# rapidshark-main-breakout-top-mk-1_B.net
KiCad netlist of a schematic drawn in EAGLE
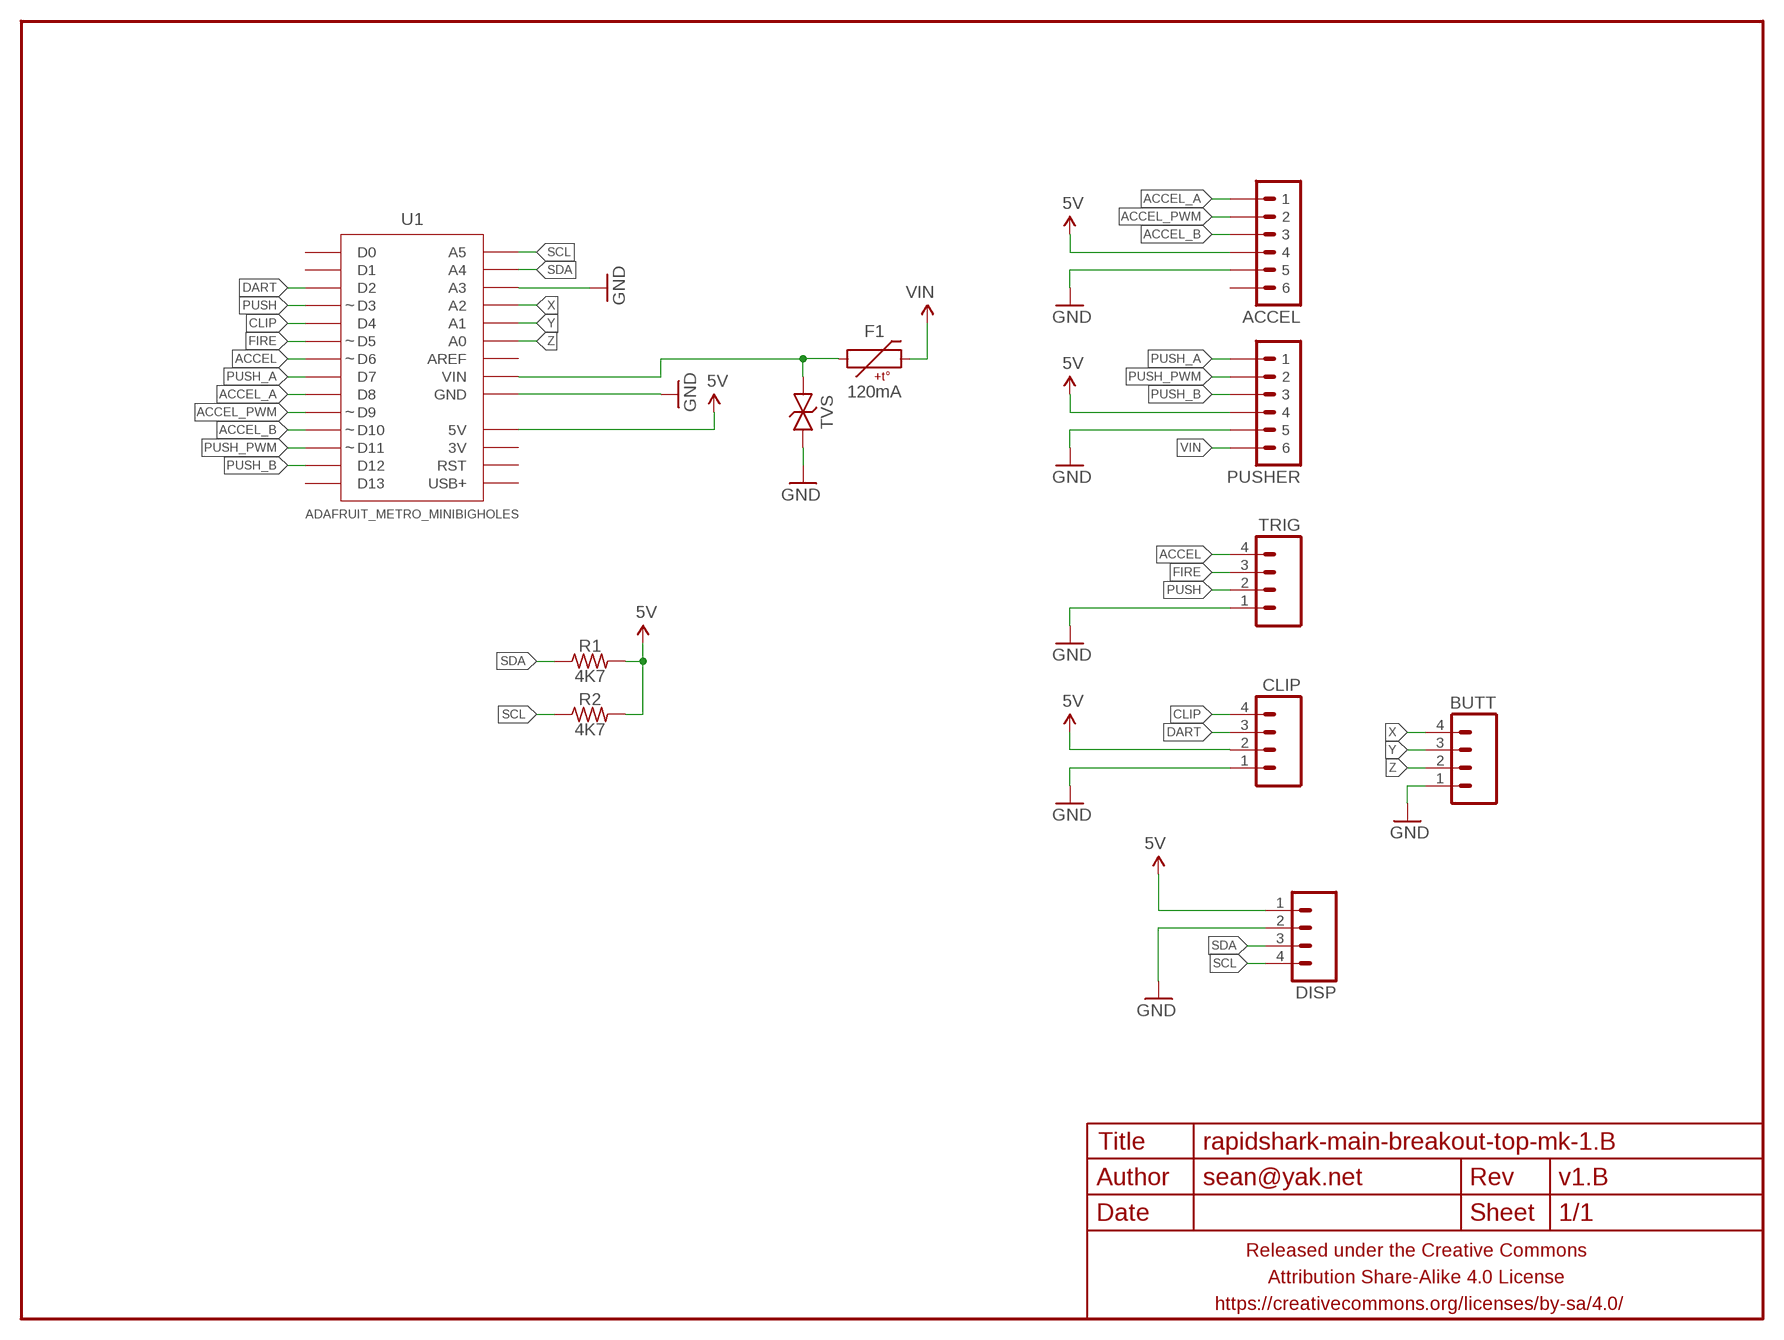
[diagram p0: schematic, sheet 1]

(export (version "E")
  (design (tool "Eeschema 10.0.6"))
  (components
    (comp (ref "ACCEL")
      (value "M06JST-PH-PTH-VERT")
      (footprint "eagle-import:JST-6-PH-VERT-PTH")
      (libsource (lib "eagle-import") (part "M06JST-PH-PTH-VERT"))
    )
    (comp (ref "BUTT")
      (value "M04JST-PTH-VERT")
      (footprint "eagle-import:JST-4-PH-VERT-PTH")
      (libsource (lib "eagle-import") (part "M04JST-PTH-VERT"))
    )
    (comp (ref "CLIP")
      (value "M04JST-PTH-VERT")
      (footprint "eagle-import:JST-4-PH-VERT-PTH")
      (libsource (lib "eagle-import") (part "M04JST-PTH-VERT"))
    )
    (comp (ref "DISP")
      (value "M04JST-PTH-VERT")
      (footprint "eagle-import:JST-4-PH-VERT-PTH")
      (libsource (lib "eagle-import") (part "M04JST-PTH-VERT"))
    )
    (comp (ref "F1")
      (value "120mA")
      (footprint "eagle-import:PTC-1206")
      (libsource (lib "eagle-import") (part "PTCSMD"))
    )
    (comp (ref "FRAME1")
      (value "FRAME-LETTERNO_PACKAGE")
      (footprint "eagle-import:DUMMY")
      (fields (field (name "DESIGNER") "sean@yak.net") (field (name "VERSION") "v1.B"))
      (libsource (lib "eagle-import") (part "FRAME-LETTERNO_PACKAGE"))
    )
    (comp (ref "PUSHER")
      (value "M06JST-PH-PTH-VERT")
      (footprint "eagle-import:JST-6-PH-VERT-PTH")
      (libsource (lib "eagle-import") (part "M06JST-PH-PTH-VERT"))
    )
    (comp (ref "R1")
      (value "4K7")
      (footprint "eagle-import:R0805")
      (libsource (lib "eagle-import") (part "RESISTORR0805"))
    )
    (comp (ref "R2")
      (value "4K7")
      (footprint "eagle-import:R0805")
      (libsource (lib "eagle-import") (part "RESISTORR0805"))
    )
    (comp (ref "TRIG")
      (value "M04JST-PTH-VERT")
      (footprint "eagle-import:JST-4-PH-VERT-PTH")
      (libsource (lib "eagle-import") (part "M04JST-PTH-VERT"))
    )
    (comp (ref "TVS")
      (value "TVSSMA")
      (footprint "eagle-import:SMA-DIODE-TVS-BIDIR")
      (libsource (lib "eagle-import") (part "TVSSMA"))
    )
    (comp (ref "U1")
      (value "ADAFRUIT_METRO_MINIBIGHOLES")
      (footprint "eagle-import:ADAFRUIT_METRO_MINI_BIGHOLES")
      (libsource (lib "eagle-import") (part "ADAFRUIT_METRO_MINIBIGHOLES"))
    )
  )
  (nets
    (net (code "1") (name "5V") (class "Default")
      (node (ref "ACCEL") (pin "4") (pinfunction "4_4") (pintype "passive"))
      (node (ref "CLIP") (pin "2") (pinfunction "2_2") (pintype "passive"))
      (node (ref "DISP") (pin "1") (pinfunction "1_1") (pintype "passive"))
      (node (ref "PUSHER") (pin "4") (pinfunction "4_4") (pintype "passive"))
      (node (ref "R1") (pin "2") (pinfunction "2_2") (pintype "passive"))
      (node (ref "R2") (pin "2") (pinfunction "2_2") (pintype "passive"))
      (node (ref "U1") (pin "18") (pinfunction "5V_18") (pintype "bidirectional"))
    )
    (net (code "2") (name "ACCEL") (class "Default")
      (node (ref "TRIG") (pin "4") (pinfunction "4_4") (pintype "passive"))
      (node (ref "U1") (pin "7") (pinfunction "D6_7") (pintype "bidirectional"))
    )
    (net (code "3") (name "ACCEL_A") (class "Default")
      (node (ref "ACCEL") (pin "1") (pinfunction "1_1") (pintype "passive"))
      (node (ref "U1") (pin "9") (pinfunction "D8_9") (pintype "bidirectional"))
    )
    (net (code "4") (name "ACCEL_B") (class "Default")
      (node (ref "ACCEL") (pin "3") (pinfunction "3_3") (pintype "passive"))
      (node (ref "U1") (pin "11") (pinfunction "D10_11") (pintype "bidirectional"))
    )
    (net (code "5") (name "ACCEL_PWM") (class "Default")
      (node (ref "ACCEL") (pin "2") (pinfunction "2_2") (pintype "passive"))
      (node (ref "U1") (pin "10") (pinfunction "D9_10") (pintype "bidirectional"))
    )
    (net (code "6") (name "CLIP") (class "Default")
      (node (ref "CLIP") (pin "4") (pinfunction "4_4") (pintype "passive"))
      (node (ref "U1") (pin "5") (pinfunction "D4_5") (pintype "bidirectional"))
    )
    (net (code "7") (name "DART") (class "Default")
      (node (ref "CLIP") (pin "3") (pinfunction "3_3") (pintype "passive"))
      (node (ref "U1") (pin "3") (pinfunction "D2_3") (pintype "bidirectional"))
    )
    (net (code "8") (name "FIRE") (class "Default")
      (node (ref "TRIG") (pin "3") (pinfunction "3_3") (pintype "passive"))
      (node (ref "U1") (pin "6") (pinfunction "D5_6") (pintype "bidirectional"))
    )
    (net (code "9") (name "GND") (class "Default")
      (node (ref "ACCEL") (pin "5") (pinfunction "5_5") (pintype "passive"))
      (node (ref "BUTT") (pin "1") (pinfunction "1_1") (pintype "passive"))
      (node (ref "CLIP") (pin "1") (pinfunction "1_1") (pintype "passive"))
      (node (ref "DISP") (pin "2") (pinfunction "2_2") (pintype "passive"))
      (node (ref "PUSHER") (pin "5") (pinfunction "5_5") (pintype "passive"))
      (node (ref "TRIG") (pin "1") (pinfunction "1_1") (pintype "passive"))
      (node (ref "TVS") (pin "1") (pinfunction "1_1") (pintype "passive"))
      (node (ref "U1") (pin "19") (pinfunction "GND_19") (pintype "bidirectional"))
      (node (ref "U1") (pin "20") (pinfunction "GND_20") (pintype "bidirectional"))
      (node (ref "U1") (pin "26") (pinfunction "A3_26") (pintype "bidirectional"))
    )
    (net (code "10") (name "Net-(U1-VIN)") (class "Default")
      (node (ref "F1") (pin "1") (pinfunction "1_1") (pintype "passive"))
      (node (ref "TVS") (pin "2") (pinfunction "2_2") (pintype "passive"))
      (node (ref "U1") (pin "21") (pinfunction "VIN_21") (pintype "bidirectional"))
    )
    (net (code "11") (name "PUSH") (class "Default")
      (node (ref "TRIG") (pin "2") (pinfunction "2_2") (pintype "passive"))
      (node (ref "U1") (pin "4") (pinfunction "D3_4") (pintype "bidirectional"))
    )
    (net (code "12") (name "PUSH_A") (class "Default")
      (node (ref "PUSHER") (pin "1") (pinfunction "1_1") (pintype "passive"))
      (node (ref "U1") (pin "8") (pinfunction "D7_8") (pintype "bidirectional"))
    )
    (net (code "13") (name "PUSH_B") (class "Default")
      (node (ref "PUSHER") (pin "3") (pinfunction "3_3") (pintype "passive"))
      (node (ref "U1") (pin "13") (pinfunction "D12_13") (pintype "bidirectional"))
    )
    (net (code "14") (name "PUSH_PWM") (class "Default")
      (node (ref "PUSHER") (pin "2") (pinfunction "2_2") (pintype "passive"))
      (node (ref "U1") (pin "12") (pinfunction "D11_12") (pintype "bidirectional"))
    )
    (net (code "15") (name "SCL") (class "Default")
      (node (ref "DISP") (pin "4") (pinfunction "4_4") (pintype "passive"))
      (node (ref "R2") (pin "1") (pinfunction "1_1") (pintype "passive"))
      (node (ref "U1") (pin "28") (pinfunction "A5_28") (pintype "bidirectional"))
    )
    (net (code "16") (name "SDA") (class "Default")
      (node (ref "DISP") (pin "3") (pinfunction "3_3") (pintype "passive"))
      (node (ref "R1") (pin "1") (pinfunction "1_1") (pintype "passive"))
      (node (ref "U1") (pin "27") (pinfunction "A4_27") (pintype "bidirectional"))
    )
    (net (code "17") (name "VIN") (class "Default")
      (node (ref "F1") (pin "2") (pinfunction "2_2") (pintype "passive"))
      (node (ref "PUSHER") (pin "6") (pinfunction "6_6") (pintype "passive"))
    )
    (net (code "18") (name "X") (class "Default")
      (node (ref "BUTT") (pin "4") (pinfunction "4_4") (pintype "passive"))
      (node (ref "U1") (pin "25") (pinfunction "A2_25") (pintype "bidirectional"))
    )
    (net (code "19") (name "Y") (class "Default")
      (node (ref "BUTT") (pin "3") (pinfunction "3_3") (pintype "passive"))
      (node (ref "U1") (pin "24") (pinfunction "A1_24") (pintype "bidirectional"))
    )
    (net (code "20") (name "Z") (class "Default")
      (node (ref "BUTT") (pin "2") (pinfunction "2_2") (pintype "passive"))
      (node (ref "U1") (pin "23") (pinfunction "A0_23") (pintype "bidirectional"))
    )
    (net (code "21") (name "unconnected-(ACCEL-Pad6)") (class "Default")
      (node (ref "ACCEL") (pin "6") (pinfunction "6_6") (pintype "passive"))
    )
    (net (code "22") (name "unconnected-(U1-3V-Pad17)") (class "Default")
      (node (ref "U1") (pin "17") (pinfunction "3V_17") (pintype "bidirectional"))
    )
    (net (code "23") (name "unconnected-(U1-AREF-Pad22)") (class "Default")
      (node (ref "U1") (pin "22") (pinfunction "AREF_22") (pintype "bidirectional"))
    )
    (net (code "24") (name "unconnected-(U1-D0-Pad1)") (class "Default")
      (node (ref "U1") (pin "1") (pinfunction "D0_1") (pintype "bidirectional"))
    )
    (net (code "25") (name "unconnected-(U1-D1-Pad2)") (class "Default")
      (node (ref "U1") (pin "2") (pinfunction "D1_2") (pintype "bidirectional"))
    )
    (net (code "26") (name "unconnected-(U1-D13-Pad14)") (class "Default")
      (node (ref "U1") (pin "14") (pinfunction "D13_14") (pintype "bidirectional"))
    )
    (net (code "27") (name "unconnected-(U1-RST-Pad16)") (class "Default")
      (node (ref "U1") (pin "16") (pinfunction "RST_16") (pintype "bidirectional"))
    )
    (net (code "28") (name "unconnected-(U1-USB+-Pad15)") (class "Default")
      (node (ref "U1") (pin "15") (pinfunction "USB+_15") (pintype "bidirectional"))
    )
  )
)
